# source_eagle.net
KiCad netlist of a schematic drawn in EAGLE
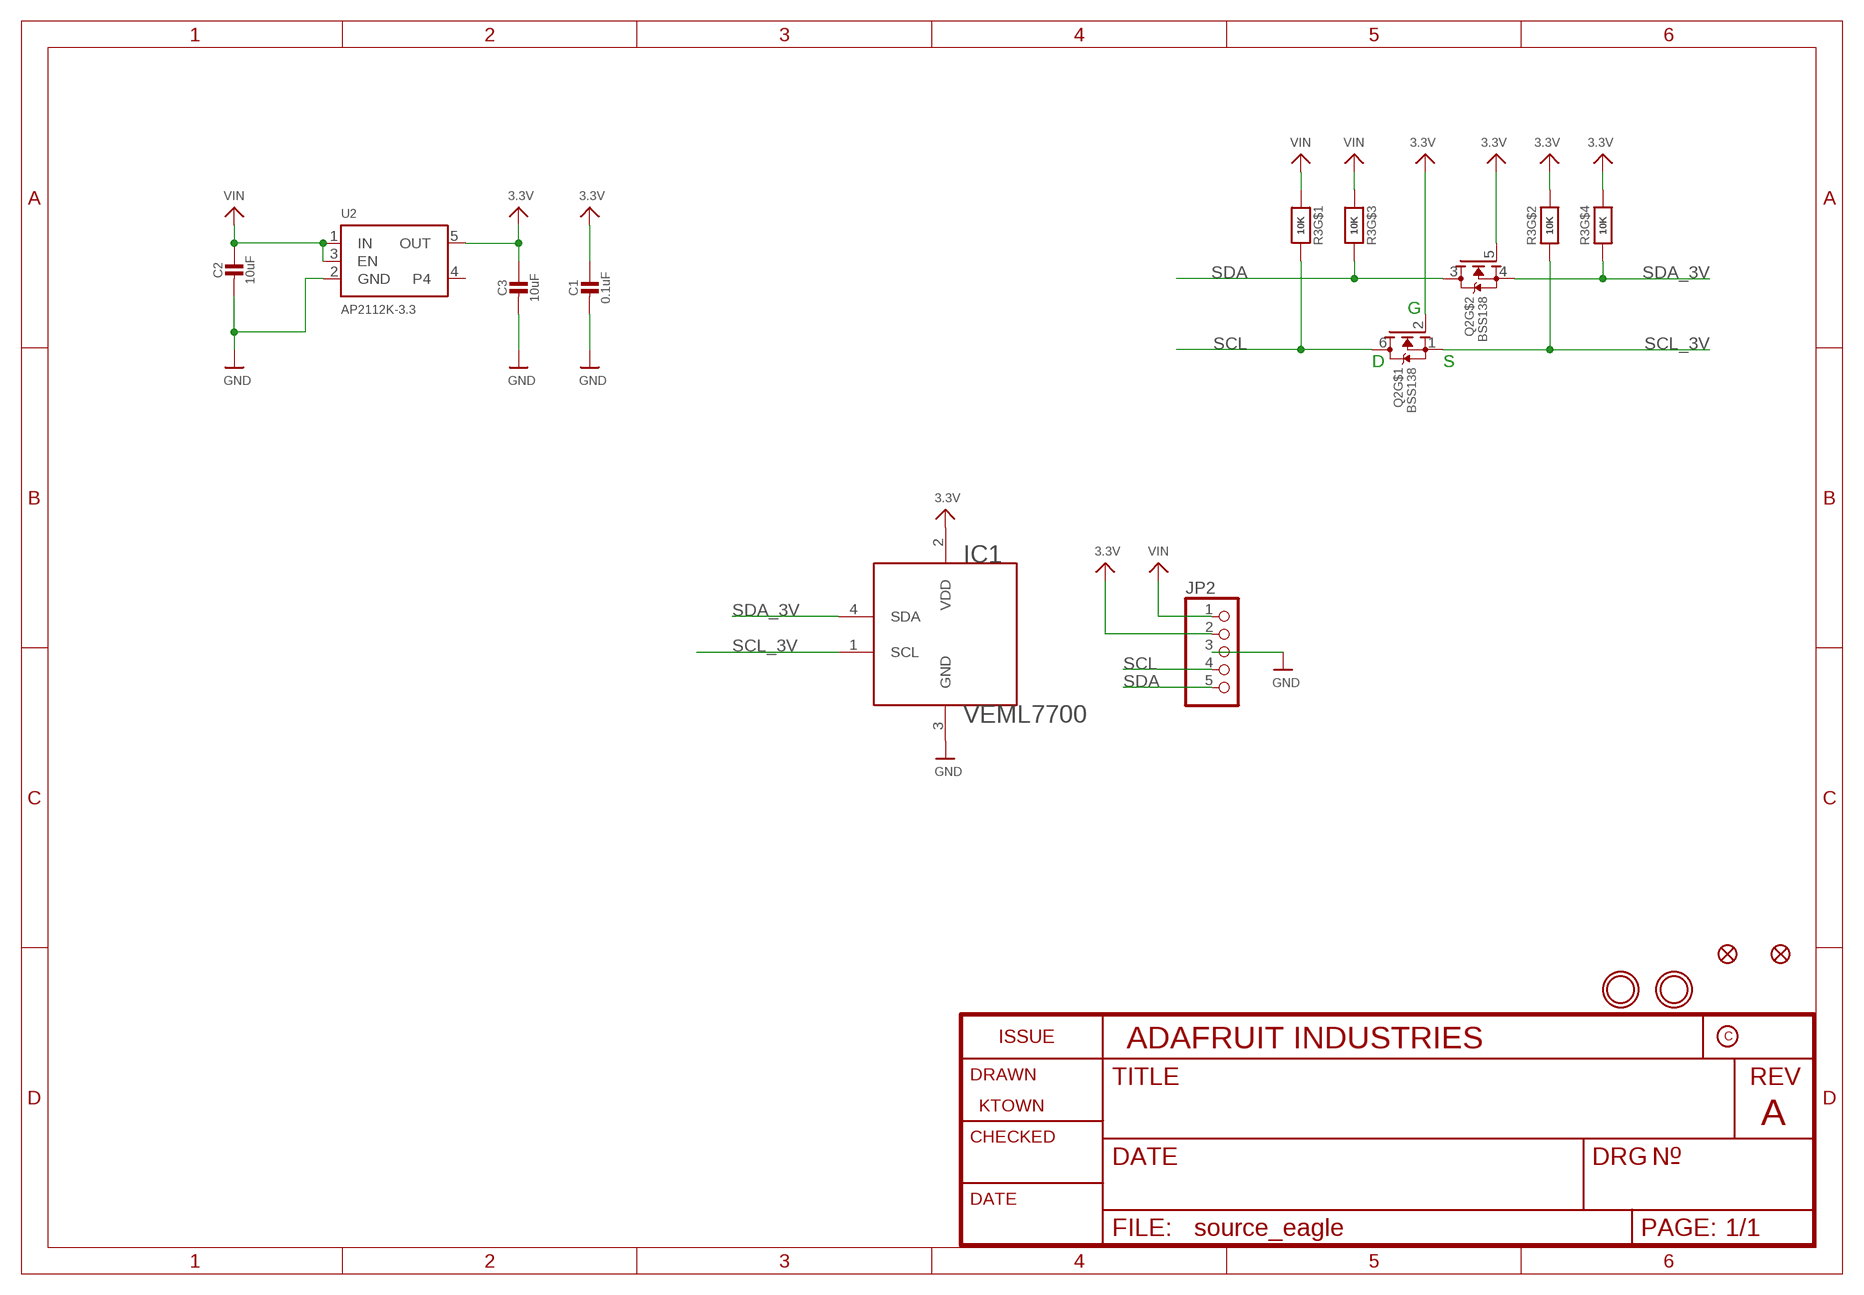
[diagram p0: schematic, sheet 1]

(export (version "E")
  (design (tool "Eeschema 10.0.6"))
  (components
    (comp (ref "C1")
      (value "0.1uF")
      (footprint "eagle-import:0603-NO")
      (libsource (lib "eagle-import") (part "CAP_CERAMIC0603_NO"))
    )
    (comp (ref "C2")
      (value "10uF")
      (footprint "eagle-import:0805-NO")
      (libsource (lib "eagle-import") (part "CAP_CERAMIC0805-NOOUTLINE"))
    )
    (comp (ref "C3")
      (value "10uF")
      (footprint "eagle-import:0805-NO")
      (libsource (lib "eagle-import") (part "CAP_CERAMIC0805-NOOUTLINE"))
    )
    (comp (ref "FID1")
      (value "FIDUCIAL_1MM")
      (footprint "eagle-import:FIDUCIAL_1MM")
      (libsource (lib "eagle-import") (part "FIDUCIAL_1MM"))
    )
    (comp (ref "FID2")
      (value "FIDUCIAL_1MM")
      (footprint "eagle-import:FIDUCIAL_1MM")
      (libsource (lib "eagle-import") (part "FIDUCIAL_1MM"))
    )
    (comp (ref "IC1")
      (value "VEML7700")
      (footprint "eagle-import:VEML7700")
      (libsource (lib "eagle-import") (part "VEML7700"))
    )
    (comp (ref "JP2")
      (value "HEADER-1X5ROUND")
      (footprint "eagle-import:1X05_ROUND")
      (libsource (lib "eagle-import") (part "HEADER-1X5ROUND"))
    )
    (comp (ref "Q2")
      (value "BSS138")
      (footprint "eagle-import:SOT363")
      (libsource (lib "eagle-import") (part "MOSFET-N_DUAL"))
    )
    (comp (ref "R3")
      (value "10K")
      (footprint "eagle-import:RESPACK_4X0603")
      (libsource (lib "eagle-import") (part "RESISTOR_4PACK"))
    )
    (comp (ref "U$3")
      (value "MOUNTINGHOLE2.5")
      (footprint "eagle-import:MOUNTINGHOLE_2.5_PLATED")
      (libsource (lib "eagle-import") (part "MOUNTINGHOLE2.5"))
    )
    (comp (ref "U$4")
      (value "MOUNTINGHOLE2.5")
      (footprint "eagle-import:MOUNTINGHOLE_2.5_PLATED")
      (libsource (lib "eagle-import") (part "MOUNTINGHOLE2.5"))
    )
    (comp (ref "U2")
      (value "AP2112K-3.3")
      (footprint "eagle-import:SOT23-5")
      (libsource (lib "eagle-import") (part "VREG_SOT23-5"))
    )
  )
  (nets
    (net (code "1") (name "/SCL") (class "Default")
      (node (ref "JP2") (pin "4") (pinfunction "4_4") (pintype "passive"))
      (node (ref "Q2") (pin "6") (pinfunction "D_6") (pintype "bidirectional"))
      (node (ref "R3") (pin "8") (pinfunction "2_8") (pintype "passive"))
    )
    (net (code "2") (name "/SCL_3V") (class "Default")
      (node (ref "IC1") (pin "1") (pinfunction "SCL_1") (pintype "bidirectional"))
      (node (ref "Q2") (pin "1") (pinfunction "S_1") (pintype "bidirectional"))
      (node (ref "R3") (pin "7") (pinfunction "2_7") (pintype "passive"))
    )
    (net (code "3") (name "/SDA") (class "Default")
      (node (ref "JP2") (pin "5") (pinfunction "5_5") (pintype "passive"))
      (node (ref "Q2") (pin "3") (pinfunction "D_3") (pintype "bidirectional"))
      (node (ref "R3") (pin "6") (pinfunction "2_6") (pintype "passive"))
    )
    (net (code "4") (name "/SDA_3V") (class "Default")
      (node (ref "IC1") (pin "4") (pinfunction "SDA_4") (pintype "bidirectional"))
      (node (ref "Q2") (pin "4") (pinfunction "S_4") (pintype "bidirectional"))
      (node (ref "R3") (pin "5") (pinfunction "2_5") (pintype "passive"))
    )
    (net (code "5") (name "3.3V") (class "Default")
      (node (ref "C1") (pin "1") (pinfunction "1_1") (pintype "passive"))
      (node (ref "C3") (pin "1") (pinfunction "1_1") (pintype "passive"))
      (node (ref "IC1") (pin "2") (pinfunction "VDD_2") (pintype "power_in"))
      (node (ref "JP2") (pin "2") (pinfunction "2_2") (pintype "passive"))
      (node (ref "Q2") (pin "2") (pinfunction "G_2") (pintype "bidirectional"))
      (node (ref "Q2") (pin "5") (pinfunction "G_5") (pintype "bidirectional"))
      (node (ref "R3") (pin "2") (pinfunction "1_2") (pintype "passive"))
      (node (ref "R3") (pin "4") (pinfunction "1_4") (pintype "passive"))
      (node (ref "U2") (pin "5") (pinfunction "OUT_5") (pintype "power_in"))
    )
    (net (code "6") (name "GND") (class "Default")
      (node (ref "C1") (pin "2") (pinfunction "2_2") (pintype "passive"))
      (node (ref "C2") (pin "2") (pinfunction "2_2") (pintype "passive"))
      (node (ref "C3") (pin "2") (pinfunction "2_2") (pintype "passive"))
      (node (ref "IC1") (pin "3") (pinfunction "GND_3") (pintype "power_in"))
      (node (ref "JP2") (pin "3") (pinfunction "3_3") (pintype "passive"))
      (node (ref "U2") (pin "2") (pinfunction "GND_2") (pintype "power_in"))
    )
    (net (code "7") (name "VIN") (class "Default")
      (node (ref "C2") (pin "1") (pinfunction "1_1") (pintype "passive"))
      (node (ref "JP2") (pin "1") (pinfunction "1_1") (pintype "passive"))
      (node (ref "R3") (pin "1") (pinfunction "1_1") (pintype "passive"))
      (node (ref "R3") (pin "3") (pinfunction "1_3") (pintype "passive"))
      (node (ref "U2") (pin "1") (pinfunction "IN_1") (pintype "power_in"))
      (node (ref "U2") (pin "3") (pinfunction "EN_3") (pintype "input"))
    )
    (net (code "8") (name "unconnected-(U2-P4-Pad4)") (class "Default")
      (node (ref "U2") (pin "4") (pinfunction "P4_4") (pintype "bidirectional"))
    )
  )
)
